# CallForHelp.net
KiCad netlist of a schematic drawn in EAGLE
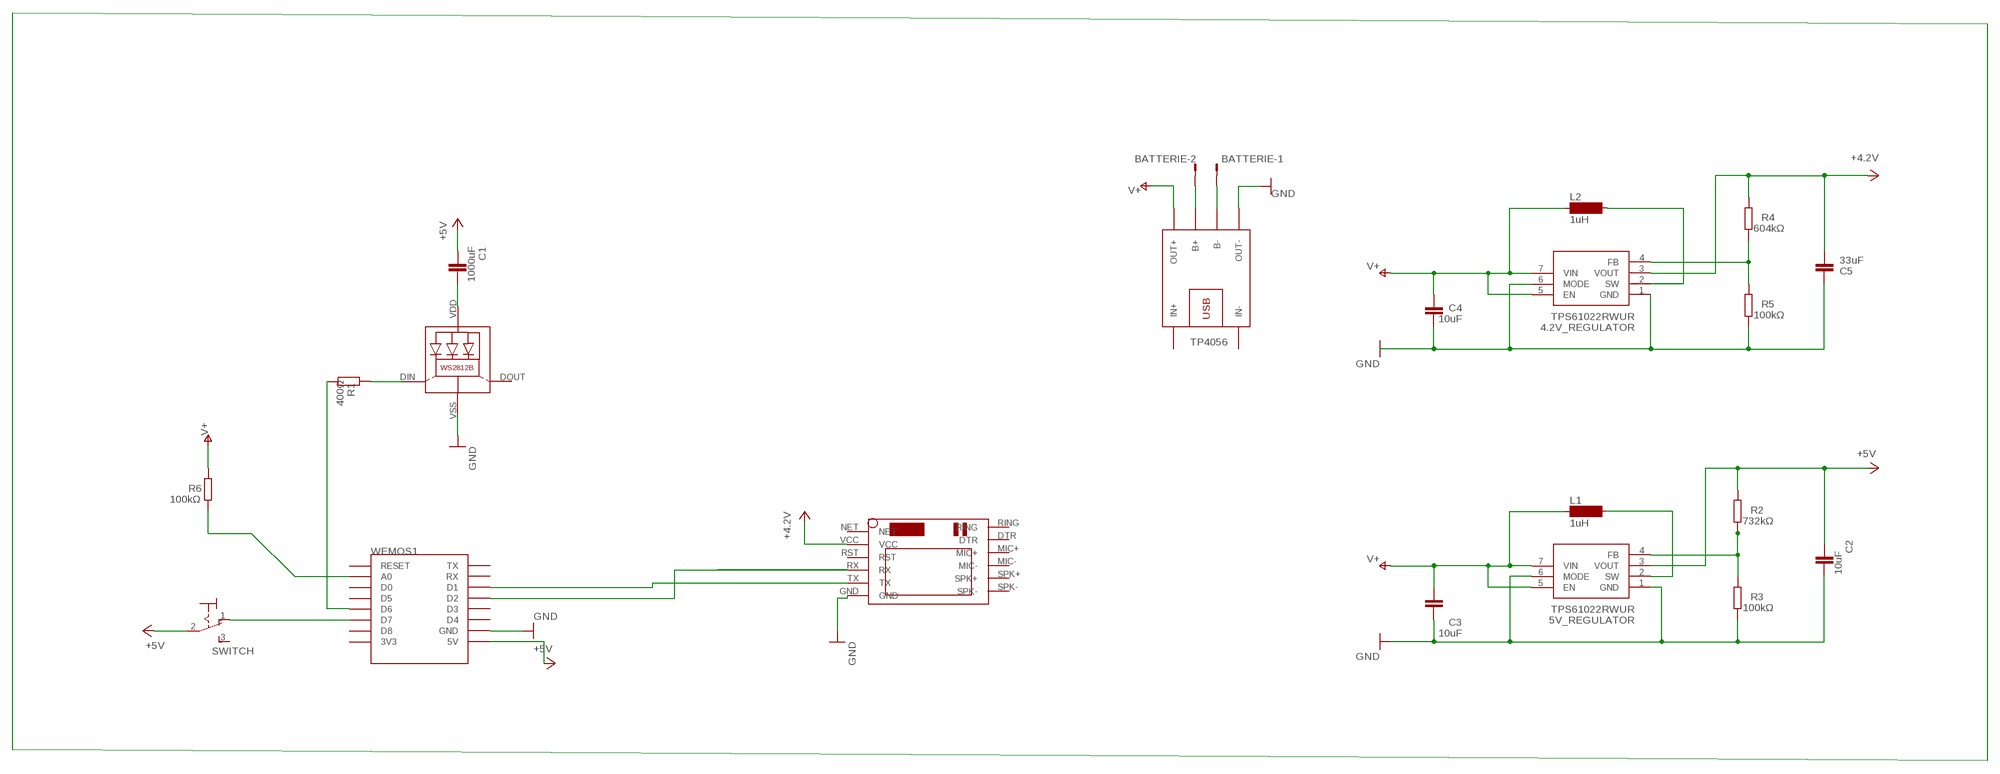
[diagram p0: schematic, sheet 1]

(export (version "E")
  (design (tool "Eeschema 10.0.6"))
  (components
    (comp (ref "4.2V_REGULATOR")
      (value "TPS61022RWUR")
      (footprint "eagle-import:TPS61022RWUR")
      (fields (field (name "MOUSER_PART_NUMBER") "595-TPS61022RWUR"))
      (libsource (lib "eagle-import") (part "TPS61022RWUR"))
    )
    (comp (ref "5V_REGULATOR")
      (value "TPS61022RWUR")
      (footprint "eagle-import:TPS61022RWUR")
      (fields (field (name "MOUSER_PART_NUMBER") "595-TPS61022RWUR"))
      (libsource (lib "eagle-import") (part "TPS61022RWUR"))
    )
    (comp (ref "BATTERIE")
      (value "L02P")
      (footprint "eagle-import:L02P")
      (libsource (lib "eagle-import") (part "L02P"))
    )
    (comp (ref "C1")
      (value "1000uF")
      (footprint "eagle-import:C2.5-3")
      (libsource (lib "eagle-import") (part "C2,5-3"))
    )
    (comp (ref "C2")
      (value "10uF")
      (footprint "eagle-import:C2.5-3")
      (libsource (lib "eagle-import") (part "C2,5-3"))
    )
    (comp (ref "C3")
      (value "10uF")
      (footprint "eagle-import:C2.5-3")
      (libsource (lib "eagle-import") (part "C2,5-3"))
    )
    (comp (ref "C4")
      (value "10uF")
      (footprint "eagle-import:C2.5-3")
      (libsource (lib "eagle-import") (part "C2,5-3"))
    )
    (comp (ref "C5")
      (value "33uF")
      (footprint "eagle-import:C2.5-3")
      (libsource (lib "eagle-import") (part "C2,5-3"))
    )
    (comp (ref "L1")
      (value "1uH")
      (footprint "eagle-import:SM-L15A")
      (libsource (lib "eagle-import") (part "SM-L15A"))
    )
    (comp (ref "L2")
      (value "1uH")
      (footprint "eagle-import:SM-L15A")
      (libsource (lib "eagle-import") (part "SM-L15A"))
    )
    (comp (ref "LED1")
      (value "WS2812B")
      (footprint "eagle-import:WS2812B")
      (libsource (lib "eagle-import") (part "WS2812B"))
    )
    (comp (ref "R1")
      (value "400Ω")
      (footprint "eagle-import:0204_7")
      (libsource (lib "eagle-import") (part "R-EU_0204/7"))
    )
    (comp (ref "R2")
      (value "732kΩ")
      (footprint "eagle-import:0204_7")
      (libsource (lib "eagle-import") (part "R-EU_0204/7"))
    )
    (comp (ref "R3")
      (value "100kΩ")
      (footprint "eagle-import:0204_7")
      (libsource (lib "eagle-import") (part "R-EU_0204/7"))
    )
    (comp (ref "R4")
      (value "604kΩ")
      (footprint "eagle-import:0204_7")
      (libsource (lib "eagle-import") (part "R-EU_0204/7"))
    )
    (comp (ref "R5")
      (value "100kΩ")
      (footprint "eagle-import:0204_7")
      (libsource (lib "eagle-import") (part "R-EU_0204/7"))
    )
    (comp (ref "R6")
      (value "100kΩ")
      (footprint "eagle-import:0204_7")
      (libsource (lib "eagle-import") (part "R-EU_0204/7"))
    )
    (comp (ref "SIM800L")
      (value "SIM800LMODULE")
      (footprint "eagle-import:SIM800LMODULE")
      (libsource (lib "eagle-import") (part "SIM800LMODULE"))
    )
    (comp (ref "SWITCH")
      (value "320-916")
      (footprint "eagle-import:320-916")
      (libsource (lib "eagle-import") (part "320-916"))
    )
    (comp (ref "TP4056")
      (value "BATTERY-CHARGER-LI-PROT")
      (footprint "eagle-import:BATTERY-CHARGER-LI-PROT")
      (libsource (lib "eagle-import") (part "BATTERY-CHARGER-LI-PROT"))
    )
    (comp (ref "WEMOS1")
      (value "WEMOS-D1-MINI")
      (footprint "eagle-import:WEMOS-D1-MINI")
      (libsource (lib "eagle-import") (part "WEMOS-D1-MINI"))
    )
  )
  (nets
    (net (code "1") (name "+4.2V") (class "Default")
      (node (ref "4.2V_REGULATOR") (pin "3") (pinfunction "VOUT_3") (pintype "bidirectional"))
      (node (ref "C5") (pin "2") (pinfunction "2_2") (pintype "passive"))
      (node (ref "R4") (pin "2") (pinfunction "2_2") (pintype "passive"))
      (node (ref "SIM800L") (pin "VCC") (pinfunction "VCC_VCC") (pintype "bidirectional"))
    )
    (net (code "2") (name "+5V") (class "Default")
      (node (ref "5V_REGULATOR") (pin "3") (pinfunction "VOUT_3") (pintype "bidirectional"))
      (node (ref "C1") (pin "1") (pinfunction "1_1") (pintype "passive"))
      (node (ref "C2") (pin "1") (pinfunction "1_1") (pintype "passive"))
      (node (ref "R2") (pin "2") (pinfunction "2_2") (pintype "passive"))
      (node (ref "SWITCH") (pin "2") (pinfunction "P_2") (pintype "passive"))
      (node (ref "WEMOS1") (pin "5V") (pinfunction "5V_5V") (pintype "bidirectional"))
    )
    (net (code "3") (name "GND") (class "Default")
      (node (ref "4.2V_REGULATOR") (pin "1") (pinfunction "GND_1") (pintype "bidirectional"))
      (node (ref "4.2V_REGULATOR") (pin "6") (pinfunction "MODE_6") (pintype "bidirectional"))
      (node (ref "5V_REGULATOR") (pin "1") (pinfunction "GND_1") (pintype "bidirectional"))
      (node (ref "5V_REGULATOR") (pin "6") (pinfunction "MODE_6") (pintype "bidirectional"))
      (node (ref "C2") (pin "2") (pinfunction "2_2") (pintype "passive"))
      (node (ref "C3") (pin "2") (pinfunction "2_2") (pintype "passive"))
      (node (ref "C4") (pin "2") (pinfunction "2_2") (pintype "passive"))
      (node (ref "C5") (pin "1") (pinfunction "1_1") (pintype "passive"))
      (node (ref "LED1") (pin "VSS") (pinfunction "GND_VSS") (pintype "power_in"))
      (node (ref "R3") (pin "1") (pinfunction "1_1") (pintype "passive"))
      (node (ref "R5") (pin "1") (pinfunction "1_1") (pintype "passive"))
      (node (ref "SIM800L") (pin "GND") (pinfunction "GND_GND") (pintype "bidirectional"))
      (node (ref "TP4056") (pin "OUT-") (pinfunction "OUT-_OUT-") (pintype "bidirectional"))
      (node (ref "WEMOS1") (pin "GND") (pinfunction "GND_GND") (pintype "bidirectional"))
    )
    (net (code "4") (name "Net-(4.2V_REGULATOR-FB)") (class "Default")
      (node (ref "4.2V_REGULATOR") (pin "4") (pinfunction "FB_4") (pintype "bidirectional"))
      (node (ref "R4") (pin "1") (pinfunction "1_1") (pintype "passive"))
      (node (ref "R5") (pin "2") (pinfunction "2_2") (pintype "passive"))
    )
    (net (code "5") (name "Net-(4.2V_REGULATOR-SW)") (class "Default")
      (node (ref "4.2V_REGULATOR") (pin "2") (pinfunction "SW_2") (pintype "bidirectional"))
      (node (ref "L2") (pin "2") (pinfunction "2_2") (pintype "passive"))
    )
    (net (code "6") (name "Net-(5V_REGULATOR-FB)") (class "Default")
      (node (ref "5V_REGULATOR") (pin "4") (pinfunction "FB_4") (pintype "bidirectional"))
      (node (ref "R2") (pin "1") (pinfunction "1_1") (pintype "passive"))
      (node (ref "R3") (pin "2") (pinfunction "2_2") (pintype "passive"))
    )
    (net (code "7") (name "Net-(5V_REGULATOR-SW)") (class "Default")
      (node (ref "5V_REGULATOR") (pin "2") (pinfunction "SW_2") (pintype "bidirectional"))
      (node (ref "L1") (pin "2") (pinfunction "2_2") (pintype "passive"))
    )
    (net (code "8") (name "Net-(BATTERIEA-S)") (class "Default")
      (node (ref "BATTERIE") (pin "1") (pinfunction "S_1") (pintype "passive"))
      (node (ref "TP4056") (pin "B-") (pinfunction "B-_B-") (pintype "bidirectional"))
    )
    (net (code "9") (name "Net-(BATTERIEB-S)") (class "Default")
      (node (ref "BATTERIE") (pin "2") (pinfunction "S_2") (pintype "passive"))
      (node (ref "TP4056") (pin "B+") (pinfunction "B+_B+") (pintype "bidirectional"))
    )
    (net (code "10") (name "Net-(C1-Pad2)") (class "Default")
      (node (ref "C1") (pin "2") (pinfunction "2_2") (pintype "passive"))
      (node (ref "LED1") (pin "VDD") (pinfunction "VDD_VDD") (pintype "power_in"))
    )
    (net (code "11") (name "Net-(LED1-DI)") (class "Default")
      (node (ref "LED1") (pin "DIN") (pinfunction "DI_DIN") (pintype "input"))
      (node (ref "R1") (pin "2") (pinfunction "2_2") (pintype "passive"))
    )
    (net (code "12") (name "Net-(R1-Pad1)") (class "Default")
      (node (ref "R1") (pin "1") (pinfunction "1_1") (pintype "passive"))
      (node (ref "WEMOS1") (pin "D6") (pinfunction "D6_D6") (pintype "bidirectional"))
    )
    (net (code "13") (name "Net-(R6-Pad1)") (class "Default")
      (node (ref "R6") (pin "1") (pinfunction "1_1") (pintype "passive"))
      (node (ref "WEMOS1") (pin "A0") (pinfunction "A0_A0") (pintype "bidirectional"))
    )
    (net (code "14") (name "Net-(SIM800L-PadRX)") (class "Default")
      (node (ref "SIM800L") (pin "RX") (pinfunction "RX_RX") (pintype "bidirectional"))
      (node (ref "WEMOS1") (pin "D2") (pinfunction "D2_D2") (pintype "bidirectional"))
    )
    (net (code "15") (name "Net-(SIM800L-PadTX)") (class "Default")
      (node (ref "SIM800L") (pin "TX") (pinfunction "TX_TX") (pintype "bidirectional"))
      (node (ref "WEMOS1") (pin "D1") (pinfunction "D1_D1") (pintype "bidirectional"))
    )
    (net (code "16") (name "Net-(SWITCH-O)") (class "Default")
      (node (ref "SWITCH") (pin "1") (pinfunction "O_1") (pintype "passive"))
      (node (ref "WEMOS1") (pin "D7") (pinfunction "D7_D7") (pintype "bidirectional"))
    )
    (net (code "17") (name "V+") (class "Default")
      (node (ref "4.2V_REGULATOR") (pin "5") (pinfunction "EN_5") (pintype "bidirectional"))
      (node (ref "4.2V_REGULATOR") (pin "7") (pinfunction "VIN_7") (pintype "bidirectional"))
      (node (ref "5V_REGULATOR") (pin "5") (pinfunction "EN_5") (pintype "bidirectional"))
      (node (ref "5V_REGULATOR") (pin "7") (pinfunction "VIN_7") (pintype "bidirectional"))
      (node (ref "C3") (pin "1") (pinfunction "1_1") (pintype "passive"))
      (node (ref "C4") (pin "1") (pinfunction "1_1") (pintype "passive"))
      (node (ref "L1") (pin "1") (pinfunction "1_1") (pintype "passive"))
      (node (ref "L2") (pin "1") (pinfunction "1_1") (pintype "passive"))
      (node (ref "R6") (pin "2") (pinfunction "2_2") (pintype "passive"))
      (node (ref "TP4056") (pin "OUT+") (pinfunction "OUT+_OUT+") (pintype "bidirectional"))
    )
    (net (code "18") (name "unconnected-(LED1-DO-PadDOUT)") (class "Default")
      (node (ref "LED1") (pin "DOUT") (pinfunction "DO_DOUT") (pintype "output"))
    )
    (net (code "19") (name "unconnected-(SIM800L-PadDTR)") (class "Default")
      (node (ref "SIM800L") (pin "DTR") (pinfunction "DTR_DTR") (pintype "bidirectional"))
    )
    (net (code "20") (name "unconnected-(SIM800L-PadMIC+)") (class "Default")
      (node (ref "SIM800L") (pin "MIC+") (pinfunction "MIC+_MIC+") (pintype "bidirectional"))
    )
    (net (code "21") (name "unconnected-(SIM800L-PadMIC-)") (class "Default")
      (node (ref "SIM800L") (pin "MIC-") (pinfunction "MIC-_MIC-") (pintype "bidirectional"))
    )
    (net (code "22") (name "unconnected-(SIM800L-PadNET)") (class "Default")
      (node (ref "SIM800L") (pin "NET") (pinfunction "NET_NET") (pintype "bidirectional"))
    )
    (net (code "23") (name "unconnected-(SIM800L-PadRING)") (class "Default")
      (node (ref "SIM800L") (pin "RING") (pinfunction "RING_RING") (pintype "bidirectional"))
    )
    (net (code "24") (name "unconnected-(SIM800L-PadRST)") (class "Default")
      (node (ref "SIM800L") (pin "RST") (pinfunction "RST_RST") (pintype "bidirectional"))
    )
    (net (code "25") (name "unconnected-(SIM800L-PadSPK+)") (class "Default")
      (node (ref "SIM800L") (pin "SPK+") (pinfunction "SPK+_SPK+") (pintype "bidirectional"))
    )
    (net (code "26") (name "unconnected-(SIM800L-PadSPK-)") (class "Default")
      (node (ref "SIM800L") (pin "SPK-") (pinfunction "SPK-_SPK-") (pintype "bidirectional"))
    )
    (net (code "27") (name "unconnected-(SWITCH-S-Pad3)") (class "Default")
      (node (ref "SWITCH") (pin "3") (pinfunction "S_3") (pintype "passive"))
    )
    (net (code "28") (name "unconnected-(TP4056-PadIN+)") (class "Default")
      (node (ref "TP4056") (pin "IN+") (pinfunction "IN+_IN+") (pintype "bidirectional"))
    )
    (net (code "29") (name "unconnected-(TP4056-PadIN-)") (class "Default")
      (node (ref "TP4056") (pin "IN-") (pinfunction "IN-_IN-") (pintype "bidirectional"))
    )
    (net (code "30") (name "unconnected-(WEMOS1-Pad3V3)") (class "Default")
      (node (ref "WEMOS1") (pin "3V3") (pinfunction "3V3_3V3") (pintype "bidirectional"))
    )
    (net (code "31") (name "unconnected-(WEMOS1-PadD0)") (class "Default")
      (node (ref "WEMOS1") (pin "D0") (pinfunction "D0_D0") (pintype "bidirectional"))
    )
    (net (code "32") (name "unconnected-(WEMOS1-PadD3)") (class "Default")
      (node (ref "WEMOS1") (pin "D3") (pinfunction "D3_D3") (pintype "bidirectional"))
    )
    (net (code "33") (name "unconnected-(WEMOS1-PadD4)") (class "Default")
      (node (ref "WEMOS1") (pin "D4") (pinfunction "D4_D4") (pintype "bidirectional"))
    )
    (net (code "34") (name "unconnected-(WEMOS1-PadD5)") (class "Default")
      (node (ref "WEMOS1") (pin "D5") (pinfunction "D5_D5") (pintype "bidirectional"))
    )
    (net (code "35") (name "unconnected-(WEMOS1-PadD8)") (class "Default")
      (node (ref "WEMOS1") (pin "D8") (pinfunction "D8_D8") (pintype "bidirectional"))
    )
    (net (code "36") (name "unconnected-(WEMOS1-PadRESET)") (class "Default")
      (node (ref "WEMOS1") (pin "RESET") (pinfunction "RESET_RESET") (pintype "bidirectional"))
    )
    (net (code "37") (name "unconnected-(WEMOS1-PadRX)") (class "Default")
      (node (ref "WEMOS1") (pin "RX") (pinfunction "RX_RX") (pintype "bidirectional"))
    )
    (net (code "38") (name "unconnected-(WEMOS1-PadTX)") (class "Default")
      (node (ref "WEMOS1") (pin "TX") (pinfunction "TX_TX") (pintype "bidirectional"))
    )
  )
)
